# passive_balancing.net
KiCad netlist of a schematic drawn in Altium Designer
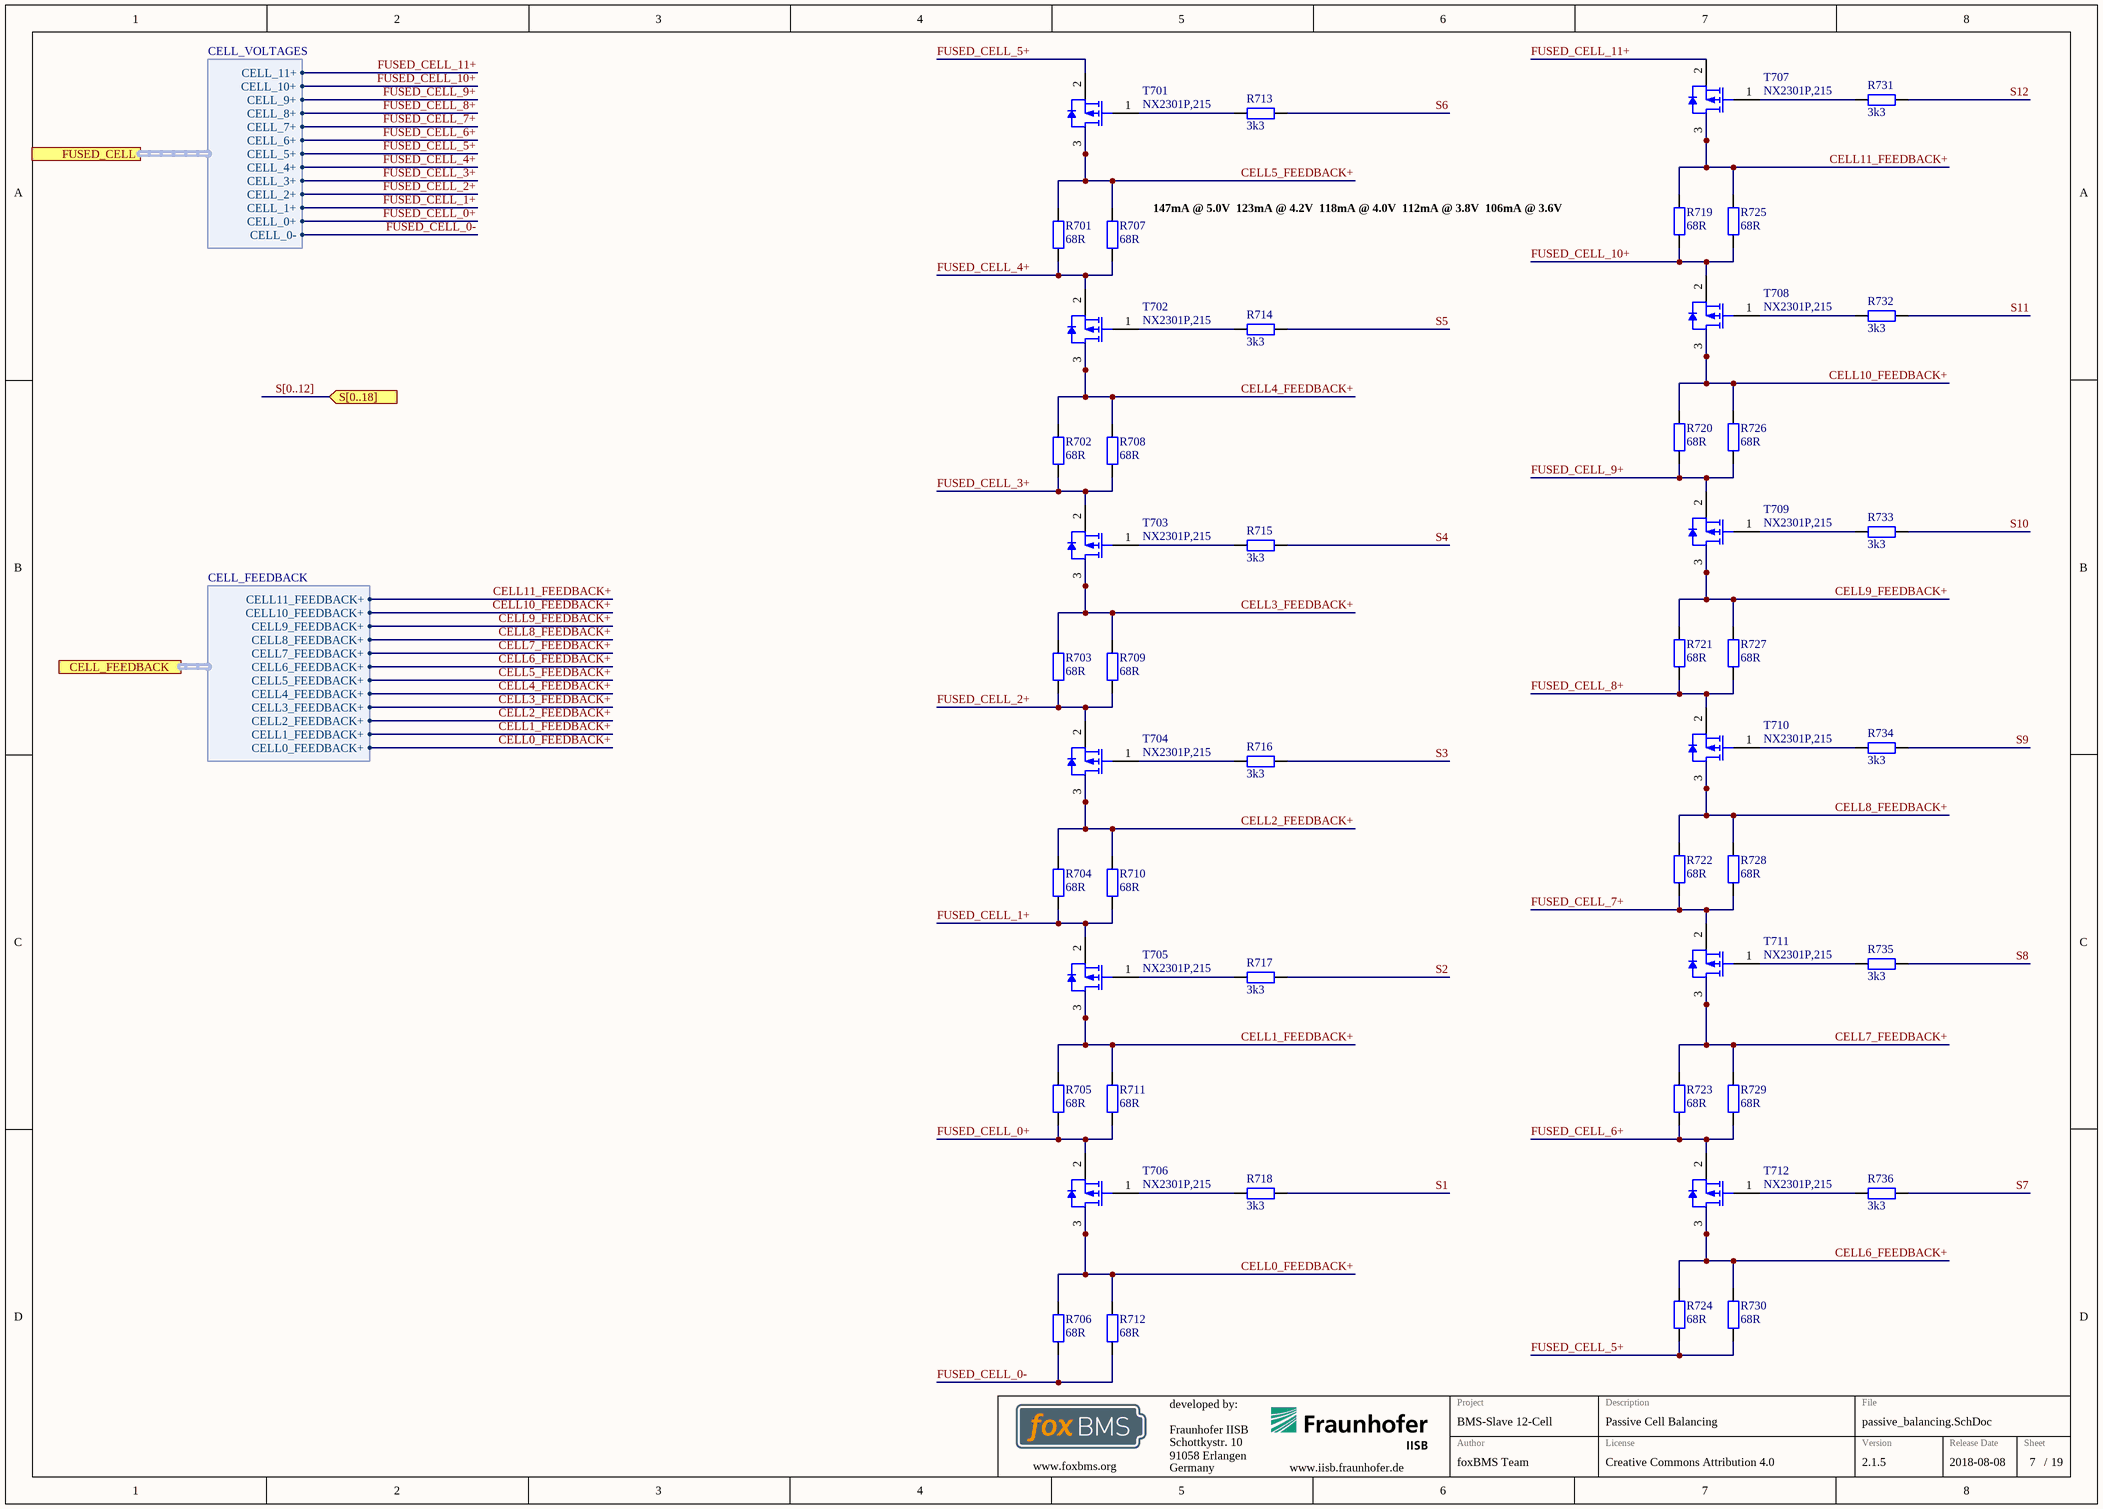
[diagram p0: passive_balancing.SchDoc]

(export (version "E")
  (design (tool "Eeschema 10.0.6"))
  (components
    (comp (ref "R701")
      (value "68R")
      (footprint "RESC5025X07N")
      (description "SMD Resistor 68R 2010")
      (fields (field (name "PART NUMBER") "gen_R_68R_2010") (field (name "TOLERANCE") "1%"))
      (libsource (lib "OE750") (part "R"))
    )
    (comp (ref "R702")
      (value "68R")
      (footprint "RESC5025X07N")
      (description "SMD Resistor 68R 2010")
      (fields (field (name "PART NUMBER") "gen_R_68R_2010") (field (name "TOLERANCE") "1%"))
      (libsource (lib "OE750") (part "R"))
    )
    (comp (ref "R703")
      (value "68R")
      (footprint "RESC5025X07N")
      (description "SMD Resistor 68R 2010")
      (fields (field (name "PART NUMBER") "gen_R_68R_2010") (field (name "TOLERANCE") "1%"))
      (libsource (lib "OE750") (part "R"))
    )
    (comp (ref "R704")
      (value "68R")
      (footprint "RESC5025X07N")
      (description "SMD Resistor 68R 2010")
      (fields (field (name "PART NUMBER") "gen_R_68R_2010") (field (name "TOLERANCE") "1%"))
      (libsource (lib "OE750") (part "R"))
    )
    (comp (ref "R705")
      (value "68R")
      (footprint "RESC5025X07N")
      (description "SMD Resistor 68R 2010")
      (fields (field (name "PART NUMBER") "gen_R_68R_2010") (field (name "TOLERANCE") "1%"))
      (libsource (lib "OE750") (part "R"))
    )
    (comp (ref "R706")
      (value "68R")
      (footprint "RESC5025X07N")
      (description "SMD Resistor 68R 2010")
      (fields (field (name "PART NUMBER") "gen_R_68R_2010") (field (name "TOLERANCE") "1%"))
      (libsource (lib "OE750") (part "R"))
    )
    (comp (ref "R707")
      (value "68R")
      (footprint "RESC5025X07N")
      (description "SMD Resistor 68R 2010")
      (fields (field (name "PART NUMBER") "gen_R_68R_2010") (field (name "TOLERANCE") "1%"))
      (libsource (lib "OE750") (part "R"))
    )
    (comp (ref "R708")
      (value "68R")
      (footprint "RESC5025X07N")
      (description "SMD Resistor 68R 2010")
      (fields (field (name "PART NUMBER") "gen_R_68R_2010") (field (name "TOLERANCE") "1%"))
      (libsource (lib "OE750") (part "R"))
    )
    (comp (ref "R709")
      (value "68R")
      (footprint "RESC5025X07N")
      (description "SMD Resistor 68R 2010")
      (fields (field (name "PART NUMBER") "gen_R_68R_2010") (field (name "TOLERANCE") "1%"))
      (libsource (lib "OE750") (part "R"))
    )
    (comp (ref "R710")
      (value "68R")
      (footprint "RESC5025X07N")
      (description "SMD Resistor 68R 2010")
      (fields (field (name "PART NUMBER") "gen_R_68R_2010") (field (name "TOLERANCE") "1%"))
      (libsource (lib "OE750") (part "R"))
    )
    (comp (ref "R711")
      (value "68R")
      (footprint "RESC5025X07N")
      (description "SMD Resistor 68R 2010")
      (fields (field (name "PART NUMBER") "gen_R_68R_2010") (field (name "TOLERANCE") "1%"))
      (libsource (lib "OE750") (part "R"))
    )
    (comp (ref "R712")
      (value "68R")
      (footprint "RESC5025X07N")
      (description "SMD Resistor 68R 2010")
      (fields (field (name "PART NUMBER") "gen_R_68R_2010") (field (name "TOLERANCE") "1%"))
      (libsource (lib "OE750") (part "R"))
    )
    (comp (ref "R713")
      (value "3k3")
      (footprint "RESC1608X05N")
      (description "SMD Resistor 3k3 0603")
      (fields (field (name "PART NUMBER") "gen_R_3k3_0603") (field (name "TOLERANCE") "1%"))
      (libsource (lib "OE750") (part "R"))
    )
    (comp (ref "R714")
      (value "3k3")
      (footprint "RESC1608X05N")
      (description "SMD Resistor 3k3 0603")
      (fields (field (name "PART NUMBER") "gen_R_3k3_0603") (field (name "TOLERANCE") "1%"))
      (libsource (lib "OE750") (part "R"))
    )
    (comp (ref "R715")
      (value "3k3")
      (footprint "RESC1608X05N")
      (description "SMD Resistor 3k3 0603")
      (fields (field (name "PART NUMBER") "gen_R_3k3_0603") (field (name "TOLERANCE") "1%"))
      (libsource (lib "OE750") (part "R"))
    )
    (comp (ref "R716")
      (value "3k3")
      (footprint "RESC1608X05N")
      (description "SMD Resistor 3k3 0603")
      (fields (field (name "PART NUMBER") "gen_R_3k3_0603") (field (name "TOLERANCE") "1%"))
      (libsource (lib "OE750") (part "R"))
    )
    (comp (ref "R717")
      (value "3k3")
      (footprint "RESC1608X05N")
      (description "SMD Resistor 3k3 0603")
      (fields (field (name "PART NUMBER") "gen_R_3k3_0603") (field (name "TOLERANCE") "1%"))
      (libsource (lib "OE750") (part "R"))
    )
    (comp (ref "R718")
      (value "3k3")
      (footprint "RESC1608X05N")
      (description "SMD Resistor 3k3 0603")
      (fields (field (name "PART NUMBER") "gen_R_3k3_0603") (field (name "TOLERANCE") "1%"))
      (libsource (lib "OE750") (part "R"))
    )
    (comp (ref "R719")
      (value "68R")
      (footprint "RESC5025X07N")
      (description "SMD Resistor 68R 2010")
      (fields (field (name "PART NUMBER") "gen_R_68R_2010") (field (name "TOLERANCE") "1%"))
      (libsource (lib "OE750") (part "R"))
    )
    (comp (ref "R720")
      (value "68R")
      (footprint "RESC5025X07N")
      (description "SMD Resistor 68R 2010")
      (fields (field (name "PART NUMBER") "gen_R_68R_2010") (field (name "TOLERANCE") "1%"))
      (libsource (lib "OE750") (part "R"))
    )
    (comp (ref "R721")
      (value "68R")
      (footprint "RESC5025X07N")
      (description "SMD Resistor 68R 2010")
      (fields (field (name "PART NUMBER") "gen_R_68R_2010") (field (name "TOLERANCE") "1%"))
      (libsource (lib "OE750") (part "R"))
    )
    (comp (ref "R722")
      (value "68R")
      (footprint "RESC5025X07N")
      (description "SMD Resistor 68R 2010")
      (fields (field (name "PART NUMBER") "gen_R_68R_2010") (field (name "TOLERANCE") "1%"))
      (libsource (lib "OE750") (part "R"))
    )
    (comp (ref "R723")
      (value "68R")
      (footprint "RESC5025X07N")
      (description "SMD Resistor 68R 2010")
      (fields (field (name "PART NUMBER") "gen_R_68R_2010") (field (name "TOLERANCE") "1%"))
      (libsource (lib "OE750") (part "R"))
    )
    (comp (ref "R724")
      (value "68R")
      (footprint "RESC5025X07N")
      (description "SMD Resistor 68R 2010")
      (fields (field (name "PART NUMBER") "gen_R_68R_2010") (field (name "TOLERANCE") "1%"))
      (libsource (lib "OE750") (part "R"))
    )
    (comp (ref "R725")
      (value "68R")
      (footprint "RESC5025X07N")
      (description "SMD Resistor 68R 2010")
      (fields (field (name "PART NUMBER") "gen_R_68R_2010") (field (name "TOLERANCE") "1%"))
      (libsource (lib "OE750") (part "R"))
    )
    (comp (ref "R726")
      (value "68R")
      (footprint "RESC5025X07N")
      (description "SMD Resistor 68R 2010")
      (fields (field (name "PART NUMBER") "gen_R_68R_2010") (field (name "TOLERANCE") "1%"))
      (libsource (lib "OE750") (part "R"))
    )
    (comp (ref "R727")
      (value "68R")
      (footprint "RESC5025X07N")
      (description "SMD Resistor 68R 2010")
      (fields (field (name "PART NUMBER") "gen_R_68R_2010") (field (name "TOLERANCE") "1%"))
      (libsource (lib "OE750") (part "R"))
    )
    (comp (ref "R728")
      (value "68R")
      (footprint "RESC5025X07N")
      (description "SMD Resistor 68R 2010")
      (fields (field (name "PART NUMBER") "gen_R_68R_2010") (field (name "TOLERANCE") "1%"))
      (libsource (lib "OE750") (part "R"))
    )
    (comp (ref "R729")
      (value "68R")
      (footprint "RESC5025X07N")
      (description "SMD Resistor 68R 2010")
      (fields (field (name "PART NUMBER") "gen_R_68R_2010") (field (name "TOLERANCE") "1%"))
      (libsource (lib "OE750") (part "R"))
    )
    (comp (ref "R730")
      (value "68R")
      (footprint "RESC5025X07N")
      (description "SMD Resistor 68R 2010")
      (fields (field (name "PART NUMBER") "gen_R_68R_2010") (field (name "TOLERANCE") "1%"))
      (libsource (lib "OE750") (part "R"))
    )
    (comp (ref "R731")
      (value "3k3")
      (footprint "RESC1608X05N")
      (description "SMD Resistor 3k3 0603")
      (fields (field (name "PART NUMBER") "gen_R_3k3_0603") (field (name "TOLERANCE") "1%"))
      (libsource (lib "OE750") (part "R"))
    )
    (comp (ref "R732")
      (value "3k3")
      (footprint "RESC1608X05N")
      (description "SMD Resistor 3k3 0603")
      (fields (field (name "PART NUMBER") "gen_R_3k3_0603") (field (name "TOLERANCE") "1%"))
      (libsource (lib "OE750") (part "R"))
    )
    (comp (ref "R733")
      (value "3k3")
      (footprint "RESC1608X05N")
      (description "SMD Resistor 3k3 0603")
      (fields (field (name "PART NUMBER") "gen_R_3k3_0603") (field (name "TOLERANCE") "1%"))
      (libsource (lib "OE750") (part "R"))
    )
    (comp (ref "R734")
      (value "3k3")
      (footprint "RESC1608X05N")
      (description "SMD Resistor 3k3 0603")
      (fields (field (name "PART NUMBER") "gen_R_3k3_0603") (field (name "TOLERANCE") "1%"))
      (libsource (lib "OE750") (part "R"))
    )
    (comp (ref "R735")
      (value "3k3")
      (footprint "RESC1608X05N")
      (description "SMD Resistor 3k3 0603")
      (fields (field (name "PART NUMBER") "gen_R_3k3_0603") (field (name "TOLERANCE") "1%"))
      (libsource (lib "OE750") (part "R"))
    )
    (comp (ref "R736")
      (value "3k3")
      (footprint "RESC1608X05N")
      (description "SMD Resistor 3k3 0603")
      (fields (field (name "PART NUMBER") "gen_R_3k3_0603") (field (name "TOLERANCE") "1%"))
      (libsource (lib "OE750") (part "R"))
    )
    (comp (ref "T701")
      (value "NX2301P,215")
      (footprint "NXP-SOT23_N")
      (description "P-Channel Trench MOSFET, -20 V, -2 A, -55 to 150 degC, 3-Pin SOT23, Tape and Reel")
      (fields (field (name "MANUFACTURER") "NXP Semiconductors"))
      (libsource (lib "Altium Content Vault") (part "NXP-PMOS-GSD-3"))
    )
    (comp (ref "T702")
      (value "NX2301P,215")
      (footprint "NXP-SOT23_N")
      (description "P-Channel Trench MOSFET, -20 V, -2 A, -55 to 150 degC, 3-Pin SOT23, Tape and Reel")
      (fields (field (name "MANUFACTURER") "NXP Semiconductors"))
      (libsource (lib "Altium Content Vault") (part "NXP-PMOS-GSD-3"))
    )
    (comp (ref "T703")
      (value "NX2301P,215")
      (footprint "NXP-SOT23_N")
      (description "P-Channel Trench MOSFET, -20 V, -2 A, -55 to 150 degC, 3-Pin SOT23, Tape and Reel")
      (fields (field (name "MANUFACTURER") "NXP Semiconductors"))
      (libsource (lib "Altium Content Vault") (part "NXP-PMOS-GSD-3"))
    )
    (comp (ref "T704")
      (value "NX2301P,215")
      (footprint "NXP-SOT23_N")
      (description "P-Channel Trench MOSFET, -20 V, -2 A, -55 to 150 degC, 3-Pin SOT23, Tape and Reel")
      (fields (field (name "MANUFACTURER") "NXP Semiconductors"))
      (libsource (lib "Altium Content Vault") (part "NXP-PMOS-GSD-3"))
    )
    (comp (ref "T705")
      (value "NX2301P,215")
      (footprint "NXP-SOT23_N")
      (description "P-Channel Trench MOSFET, -20 V, -2 A, -55 to 150 degC, 3-Pin SOT23, Tape and Reel")
      (fields (field (name "MANUFACTURER") "NXP Semiconductors"))
      (libsource (lib "Altium Content Vault") (part "NXP-PMOS-GSD-3"))
    )
    (comp (ref "T706")
      (value "NX2301P,215")
      (footprint "NXP-SOT23_N")
      (description "P-Channel Trench MOSFET, -20 V, -2 A, -55 to 150 degC, 3-Pin SOT23, Tape and Reel")
      (fields (field (name "MANUFACTURER") "NXP Semiconductors"))
      (libsource (lib "Altium Content Vault") (part "NXP-PMOS-GSD-3"))
    )
    (comp (ref "T707")
      (value "NX2301P,215")
      (footprint "NXP-SOT23_N")
      (description "P-Channel Trench MOSFET, -20 V, -2 A, -55 to 150 degC, 3-Pin SOT23, Tape and Reel")
      (fields (field (name "MANUFACTURER") "NXP Semiconductors"))
      (libsource (lib "Altium Content Vault") (part "NXP-PMOS-GSD-3"))
    )
    (comp (ref "T708")
      (value "NX2301P,215")
      (footprint "NXP-SOT23_N")
      (description "P-Channel Trench MOSFET, -20 V, -2 A, -55 to 150 degC, 3-Pin SOT23, Tape and Reel")
      (fields (field (name "MANUFACTURER") "NXP Semiconductors"))
      (libsource (lib "Altium Content Vault") (part "NXP-PMOS-GSD-3"))
    )
    (comp (ref "T709")
      (value "NX2301P,215")
      (footprint "NXP-SOT23_N")
      (description "P-Channel Trench MOSFET, -20 V, -2 A, -55 to 150 degC, 3-Pin SOT23, Tape and Reel")
      (fields (field (name "MANUFACTURER") "NXP Semiconductors"))
      (libsource (lib "Altium Content Vault") (part "NXP-PMOS-GSD-3"))
    )
    (comp (ref "T710")
      (value "NX2301P,215")
      (footprint "NXP-SOT23_N")
      (description "P-Channel Trench MOSFET, -20 V, -2 A, -55 to 150 degC, 3-Pin SOT23, Tape and Reel")
      (fields (field (name "MANUFACTURER") "NXP Semiconductors"))
      (libsource (lib "Altium Content Vault") (part "NXP-PMOS-GSD-3"))
    )
    (comp (ref "T711")
      (value "NX2301P,215")
      (footprint "NXP-SOT23_N")
      (description "P-Channel Trench MOSFET, -20 V, -2 A, -55 to 150 degC, 3-Pin SOT23, Tape and Reel")
      (fields (field (name "MANUFACTURER") "NXP Semiconductors"))
      (libsource (lib "Altium Content Vault") (part "NXP-PMOS-GSD-3"))
    )
    (comp (ref "T712")
      (value "NX2301P,215")
      (footprint "NXP-SOT23_N")
      (description "P-Channel Trench MOSFET, -20 V, -2 A, -55 to 150 degC, 3-Pin SOT23, Tape and Reel")
      (fields (field (name "MANUFACTURER") "NXP Semiconductors"))
      (libsource (lib "Altium Content Vault") (part "NXP-PMOS-GSD-3"))
    )
  )
  (nets
    (net (code "4") (name "/CELL0_FEEDBACK+") (class "Default")
      (node (ref "R706") (pin "2") (pinfunction "2_2") (pintype "passive"))
      (node (ref "R712") (pin "2") (pinfunction "2_2") (pintype "passive"))
      (node (ref "T706") (pin "3") (pinfunction "D_3") (pintype "passive"))
    )
    (net (code "5") (name "/CELL1_FEEDBACK+") (class "Default")
      (node (ref "R705") (pin "2") (pinfunction "2_2") (pintype "passive"))
      (node (ref "R711") (pin "2") (pinfunction "2_2") (pintype "passive"))
      (node (ref "T705") (pin "3") (pinfunction "D_3") (pintype "passive"))
    )
    (net (code "6") (name "/CELL2_FEEDBACK+") (class "Default")
      (node (ref "R704") (pin "2") (pinfunction "2_2") (pintype "passive"))
      (node (ref "R710") (pin "2") (pinfunction "2_2") (pintype "passive"))
      (node (ref "T704") (pin "3") (pinfunction "D_3") (pintype "passive"))
    )
    (net (code "7") (name "/CELL3_FEEDBACK+") (class "Default")
      (node (ref "R703") (pin "2") (pinfunction "2_2") (pintype "passive"))
      (node (ref "R709") (pin "2") (pinfunction "2_2") (pintype "passive"))
      (node (ref "T703") (pin "3") (pinfunction "D_3") (pintype "passive"))
    )
    (net (code "8") (name "/CELL4_FEEDBACK+") (class "Default")
      (node (ref "R702") (pin "2") (pinfunction "2_2") (pintype "passive"))
      (node (ref "R708") (pin "2") (pinfunction "2_2") (pintype "passive"))
      (node (ref "T702") (pin "3") (pinfunction "D_3") (pintype "passive"))
    )
    (net (code "9") (name "/CELL5_FEEDBACK+") (class "Default")
      (node (ref "R701") (pin "2") (pinfunction "2_2") (pintype "passive"))
      (node (ref "R707") (pin "2") (pinfunction "2_2") (pintype "passive"))
      (node (ref "T701") (pin "3") (pinfunction "D_3") (pintype "passive"))
    )
    (net (code "10") (name "/CELL6_FEEDBACK+") (class "Default")
      (node (ref "R724") (pin "2") (pinfunction "2_2") (pintype "passive"))
      (node (ref "R730") (pin "2") (pinfunction "2_2") (pintype "passive"))
      (node (ref "T712") (pin "3") (pinfunction "D_3") (pintype "passive"))
    )
    (net (code "11") (name "/CELL7_FEEDBACK+") (class "Default")
      (node (ref "R723") (pin "2") (pinfunction "2_2") (pintype "passive"))
      (node (ref "R729") (pin "2") (pinfunction "2_2") (pintype "passive"))
      (node (ref "T711") (pin "3") (pinfunction "D_3") (pintype "passive"))
    )
    (net (code "12") (name "/CELL8_FEEDBACK+") (class "Default")
      (node (ref "R722") (pin "2") (pinfunction "2_2") (pintype "passive"))
      (node (ref "R728") (pin "2") (pinfunction "2_2") (pintype "passive"))
      (node (ref "T710") (pin "3") (pinfunction "D_3") (pintype "passive"))
    )
    (net (code "13") (name "/CELL9_FEEDBACK+") (class "Default")
      (node (ref "R721") (pin "2") (pinfunction "2_2") (pintype "passive"))
      (node (ref "R727") (pin "2") (pinfunction "2_2") (pintype "passive"))
      (node (ref "T709") (pin "3") (pinfunction "D_3") (pintype "passive"))
    )
    (net (code "14") (name "/CELL10_FEEDBACK+") (class "Default")
      (node (ref "R720") (pin "2") (pinfunction "2_2") (pintype "passive"))
      (node (ref "R726") (pin "2") (pinfunction "2_2") (pintype "passive"))
      (node (ref "T708") (pin "3") (pinfunction "D_3") (pintype "passive"))
    )
    (net (code "15") (name "/CELL11_FEEDBACK+") (class "Default")
      (node (ref "R719") (pin "2") (pinfunction "2_2") (pintype "passive"))
      (node (ref "R725") (pin "2") (pinfunction "2_2") (pintype "passive"))
      (node (ref "T707") (pin "3") (pinfunction "D_3") (pintype "passive"))
    )
    (net (code "16") (name "/FUSED_CELL_0+") (class "Default")
      (node (ref "R705") (pin "1") (pinfunction "1_1") (pintype "passive"))
      (node (ref "R711") (pin "1") (pinfunction "1_1") (pintype "passive"))
      (node (ref "T706") (pin "2") (pinfunction "S_2") (pintype "passive"))
    )
    (net (code "17") (name "/FUSED_CELL_0-") (class "Default")
      (node (ref "R706") (pin "1") (pinfunction "1_1") (pintype "passive"))
      (node (ref "R712") (pin "1") (pinfunction "1_1") (pintype "passive"))
    )
    (net (code "18") (name "/FUSED_CELL_1+") (class "Default")
      (node (ref "R704") (pin "1") (pinfunction "1_1") (pintype "passive"))
      (node (ref "R710") (pin "1") (pinfunction "1_1") (pintype "passive"))
      (node (ref "T705") (pin "2") (pinfunction "S_2") (pintype "passive"))
    )
    (net (code "19") (name "/FUSED_CELL_2+") (class "Default")
      (node (ref "R703") (pin "1") (pinfunction "1_1") (pintype "passive"))
      (node (ref "R709") (pin "1") (pinfunction "1_1") (pintype "passive"))
      (node (ref "T704") (pin "2") (pinfunction "S_2") (pintype "passive"))
    )
    (net (code "20") (name "/FUSED_CELL_3+") (class "Default")
      (node (ref "R702") (pin "1") (pinfunction "1_1") (pintype "passive"))
      (node (ref "R708") (pin "1") (pinfunction "1_1") (pintype "passive"))
      (node (ref "T703") (pin "2") (pinfunction "S_2") (pintype "passive"))
    )
    (net (code "21") (name "/FUSED_CELL_4+") (class "Default")
      (node (ref "R701") (pin "1") (pinfunction "1_1") (pintype "passive"))
      (node (ref "R707") (pin "1") (pinfunction "1_1") (pintype "passive"))
      (node (ref "T702") (pin "2") (pinfunction "S_2") (pintype "passive"))
    )
    (net (code "22") (name "/FUSED_CELL_5+") (class "Default")
      (node (ref "R724") (pin "1") (pinfunction "1_1") (pintype "passive"))
      (node (ref "R730") (pin "1") (pinfunction "1_1") (pintype "passive"))
      (node (ref "T701") (pin "2") (pinfunction "S_2") (pintype "passive"))
    )
    (net (code "23") (name "/FUSED_CELL_6+") (class "Default")
      (node (ref "R723") (pin "1") (pinfunction "1_1") (pintype "passive"))
      (node (ref "R729") (pin "1") (pinfunction "1_1") (pintype "passive"))
      (node (ref "T712") (pin "2") (pinfunction "S_2") (pintype "passive"))
    )
    (net (code "24") (name "/FUSED_CELL_7+") (class "Default")
      (node (ref "R722") (pin "1") (pinfunction "1_1") (pintype "passive"))
      (node (ref "R728") (pin "1") (pinfunction "1_1") (pintype "passive"))
      (node (ref "T711") (pin "2") (pinfunction "S_2") (pintype "passive"))
    )
    (net (code "25") (name "/FUSED_CELL_8+") (class "Default")
      (node (ref "R721") (pin "1") (pinfunction "1_1") (pintype "passive"))
      (node (ref "R727") (pin "1") (pinfunction "1_1") (pintype "passive"))
      (node (ref "T710") (pin "2") (pinfunction "S_2") (pintype "passive"))
    )
    (net (code "26") (name "/FUSED_CELL_9+") (class "Default")
      (node (ref "R720") (pin "1") (pinfunction "1_1") (pintype "passive"))
      (node (ref "R726") (pin "1") (pinfunction "1_1") (pintype "passive"))
      (node (ref "T709") (pin "2") (pinfunction "S_2") (pintype "passive"))
    )
    (net (code "27") (name "/FUSED_CELL_10+") (class "Default")
      (node (ref "R719") (pin "1") (pinfunction "1_1") (pintype "passive"))
      (node (ref "R725") (pin "1") (pinfunction "1_1") (pintype "passive"))
      (node (ref "T708") (pin "2") (pinfunction "S_2") (pintype "passive"))
    )
    (net (code "28") (name "/FUSED_CELL_11+") (class "Default")
      (node (ref "T707") (pin "2") (pinfunction "S_2") (pintype "passive"))
    )
    (net (code "29") (name "/S1") (class "Default")
      (node (ref "R718") (pin "2") (pinfunction "2_2") (pintype "passive"))
    )
    (net (code "30") (name "/S2") (class "Default")
      (node (ref "R717") (pin "2") (pinfunction "2_2") (pintype "passive"))
    )
    (net (code "31") (name "/S3") (class "Default")
      (node (ref "R716") (pin "2") (pinfunction "2_2") (pintype "passive"))
    )
    (net (code "32") (name "/S4") (class "Default")
      (node (ref "R715") (pin "2") (pinfunction "2_2") (pintype "passive"))
    )
    (net (code "33") (name "/S5") (class "Default")
      (node (ref "R714") (pin "2") (pinfunction "2_2") (pintype "passive"))
    )
    (net (code "34") (name "/S6") (class "Default")
      (node (ref "R713") (pin "2") (pinfunction "2_2") (pintype "passive"))
    )
    (net (code "35") (name "/S7") (class "Default")
      (node (ref "R736") (pin "2") (pinfunction "2_2") (pintype "passive"))
    )
    (net (code "36") (name "/S8") (class "Default")
      (node (ref "R735") (pin "2") (pinfunction "2_2") (pintype "passive"))
    )
    (net (code "37") (name "/S9") (class "Default")
      (node (ref "R734") (pin "2") (pinfunction "2_2") (pintype "passive"))
    )
    (net (code "38") (name "/S10") (class "Default")
      (node (ref "R733") (pin "2") (pinfunction "2_2") (pintype "passive"))
    )
    (net (code "39") (name "/S11") (class "Default")
      (node (ref "R732") (pin "2") (pinfunction "2_2") (pintype "passive"))
    )
    (net (code "40") (name "/S12") (class "Default")
      (node (ref "R731") (pin "2") (pinfunction "2_2") (pintype "passive"))
    )
    (net (code "44") (name "Net-(T701-G)") (class "Default")
      (node (ref "R713") (pin "1") (pinfunction "1_1") (pintype "passive"))
      (node (ref "T701") (pin "1") (pinfunction "G_1") (pintype "passive"))
    )
    (net (code "45") (name "Net-(T702-G)") (class "Default")
      (node (ref "R714") (pin "1") (pinfunction "1_1") (pintype "passive"))
      (node (ref "T702") (pin "1") (pinfunction "G_1") (pintype "passive"))
    )
    (net (code "46") (name "Net-(T703-G)") (class "Default")
      (node (ref "R715") (pin "1") (pinfunction "1_1") (pintype "passive"))
      (node (ref "T703") (pin "1") (pinfunction "G_1") (pintype "passive"))
    )
    (net (code "47") (name "Net-(T704-G)") (class "Default")
      (node (ref "R716") (pin "1") (pinfunction "1_1") (pintype "passive"))
      (node (ref "T704") (pin "1") (pinfunction "G_1") (pintype "passive"))
    )
    (net (code "48") (name "Net-(T705-G)") (class "Default")
      (node (ref "R717") (pin "1") (pinfunction "1_1") (pintype "passive"))
      (node (ref "T705") (pin "1") (pinfunction "G_1") (pintype "passive"))
    )
    (net (code "49") (name "Net-(T706-G)") (class "Default")
      (node (ref "R718") (pin "1") (pinfunction "1_1") (pintype "passive"))
      (node (ref "T706") (pin "1") (pinfunction "G_1") (pintype "passive"))
    )
    (net (code "50") (name "Net-(T707-G)") (class "Default")
      (node (ref "R731") (pin "1") (pinfunction "1_1") (pintype "passive"))
      (node (ref "T707") (pin "1") (pinfunction "G_1") (pintype "passive"))
    )
    (net (code "51") (name "Net-(T708-G)") (class "Default")
      (node (ref "R732") (pin "1") (pinfunction "1_1") (pintype "passive"))
      (node (ref "T708") (pin "1") (pinfunction "G_1") (pintype "passive"))
    )
    (net (code "52") (name "Net-(T709-G)") (class "Default")
      (node (ref "R733") (pin "1") (pinfunction "1_1") (pintype "passive"))
      (node (ref "T709") (pin "1") (pinfunction "G_1") (pintype "passive"))
    )
    (net (code "53") (name "Net-(T710-G)") (class "Default")
      (node (ref "R734") (pin "1") (pinfunction "1_1") (pintype "passive"))
      (node (ref "T710") (pin "1") (pinfunction "G_1") (pintype "passive"))
    )
    (net (code "54") (name "Net-(T711-G)") (class "Default")
      (node (ref "R735") (pin "1") (pinfunction "1_1") (pintype "passive"))
      (node (ref "T711") (pin "1") (pinfunction "G_1") (pintype "passive"))
    )
    (net (code "55") (name "Net-(T712-G)") (class "Default")
      (node (ref "R736") (pin "1") (pinfunction "1_1") (pintype "passive"))
      (node (ref "T712") (pin "1") (pinfunction "G_1") (pintype "passive"))
    )
  )
)
